# MiniScope.net
KiCad netlist of a schematic drawn in Altium Designer
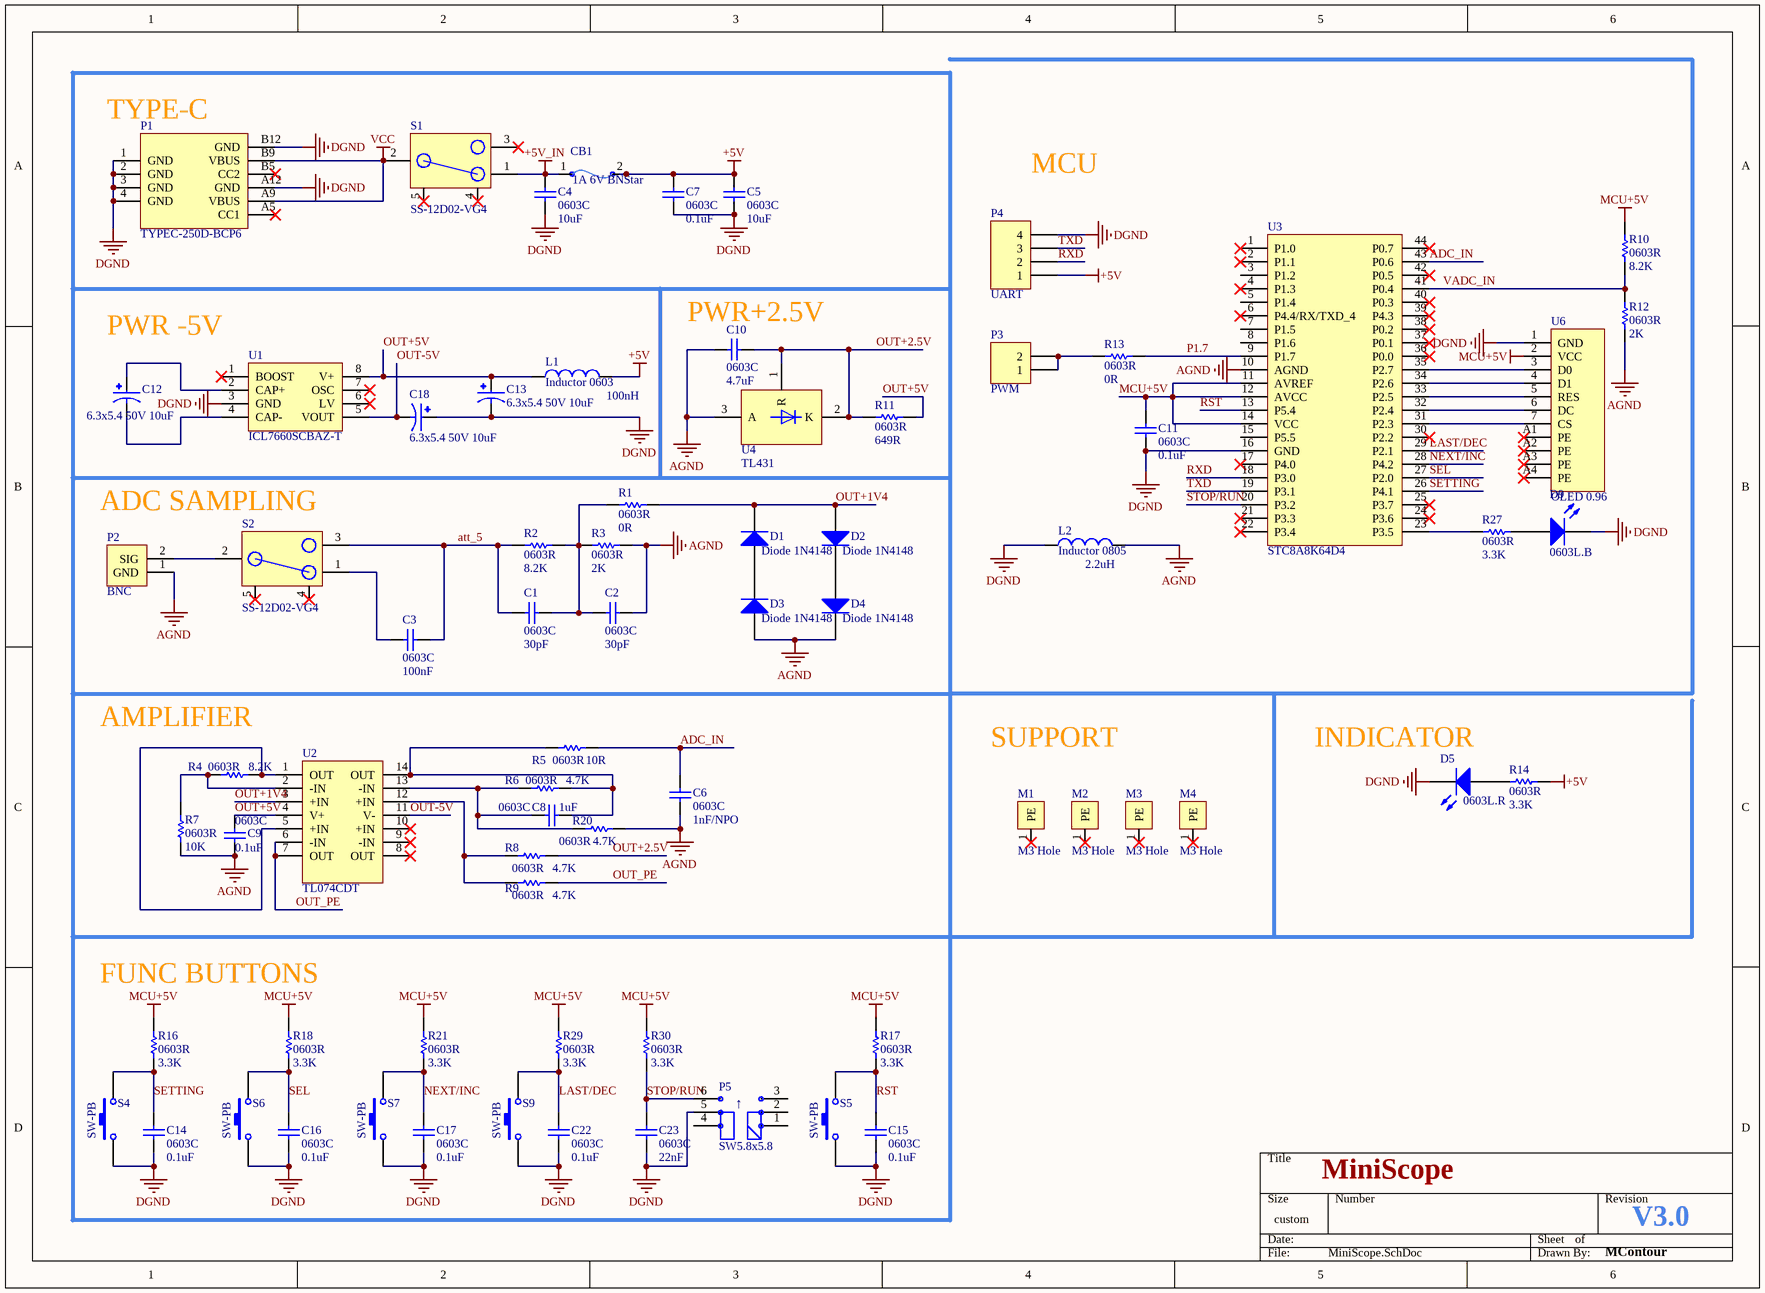
[diagram p0: MiniScope.SchDoc]

(export (version "E")
  (design (tool "Eeschema 10.0.6"))
  (components
    (comp (ref "C1")
      (value "0603C")
      (footprint "0603C")
      (description "Capacitor")
      (fields (field (name "ALTIUM_VALUE") "30pF") (field (name "PUBLISHER") "Altium Limited"))
      (libsource (lib "Miscellaneous Devices") (part "Cap"))
    )
    (comp (ref "C2")
      (value "0603C")
      (footprint "0603C")
      (description "Capacitor")
      (fields (field (name "ALTIUM_VALUE") "30pF") (field (name "PUBLISHER") "Altium Limited"))
      (libsource (lib "Miscellaneous Devices") (part "Cap"))
    )
    (comp (ref "C3")
      (value "0603C")
      (footprint "0603C")
      (description "Capacitor")
      (fields (field (name "ALTIUM_VALUE") "100nF") (field (name "PUBLISHER") "Altium Limited"))
      (libsource (lib "Miscellaneous Devices") (part "Cap"))
    )
    (comp (ref "C4")
      (value "0603C")
      (footprint "0603C")
      (description "Capacitor")
      (fields (field (name "ALTIUM_VALUE") "10uF") (field (name "PUBLISHER") "Altium Limited"))
      (libsource (lib "Miscellaneous Devices") (part "Cap"))
    )
    (comp (ref "C5")
      (value "0603C")
      (footprint "0603C")
      (description "Capacitor")
      (fields (field (name "ALTIUM_VALUE") "10uF") (field (name "PUBLISHER") "Altium Limited"))
      (libsource (lib "Miscellaneous Devices") (part "Cap"))
    )
    (comp (ref "C6")
      (value "0603C")
      (footprint "0603C")
      (description "Capacitor")
      (fields (field (name "ALTIUM_VALUE") "1nF/NPO") (field (name "PUBLISHER") "Altium Limited"))
      (libsource (lib "Miscellaneous Devices") (part "Cap"))
    )
    (comp (ref "C7")
      (value "0603C")
      (footprint "0603C")
      (description "Capacitor")
      (fields (field (name "ALTIUM_VALUE") "0.1uF") (field (name "PUBLISHER") "Altium Limited"))
      (libsource (lib "Miscellaneous Devices") (part "Cap"))
    )
    (comp (ref "C8")
      (value "0603C")
      (footprint "0603C")
      (description "Capacitor")
      (fields (field (name "ALTIUM_VALUE") "1uF") (field (name "PUBLISHER") "Altium Limited"))
      (libsource (lib "Miscellaneous Devices") (part "Cap"))
    )
    (comp (ref "C9")
      (value "0603C")
      (footprint "0603C")
      (description "Capacitor")
      (fields (field (name "ALTIUM_VALUE") "0.1uF") (field (name "PUBLISHER") "Altium Limited"))
      (libsource (lib "Miscellaneous Devices") (part "Cap"))
    )
    (comp (ref "C10")
      (value "0603C")
      (footprint "0603C")
      (description "Capacitor")
      (fields (field (name "ALTIUM_VALUE") "4.7uF") (field (name "PUBLISHER") "Altium Limited"))
      (libsource (lib "Miscellaneous Devices") (part "Cap"))
    )
    (comp (ref "C11")
      (value "0603C")
      (footprint "0603C")
      (description "Capacitor")
      (fields (field (name "ALTIUM_VALUE") "0.1uF") (field (name "PUBLISHER") "Altium Limited"))
      (libsource (lib "Miscellaneous Devices") (part "Cap"))
    )
    (comp (ref "C12")
      (value "6.3x5.4 50V 10uF")
      (footprint "CAP 6.3x5.4")
      (description "Cap Aluminum Lytic 10uF 50V 20% (6.3 X 5.4mm) SMD")
      (fields (field (name "MF") "Panasonic") (field (name "MP") "EEE-1AA330NP"))
      (libsource (lib "MiniScope") (part "6.3x5.4 50V 10uF"))
    )
    (comp (ref "C13")
      (value "6.3x5.4 50V 10uF")
      (footprint "CAP 6.3x5.4")
      (description "Cap Aluminum Lytic 10uF 50V 20% (6.3 X 5.4mm) SMD")
      (fields (field (name "MF") "Panasonic") (field (name "MP") "EEE-1AA330NP"))
      (libsource (lib "MiniScope") (part "6.3x5.4 50V 10uF"))
    )
    (comp (ref "C14")
      (value "0603C")
      (footprint "0603C")
      (description "Capacitor")
      (fields (field (name "ALTIUM_VALUE") "0.1uF") (field (name "PUBLISHER") "Altium Limited"))
      (libsource (lib "Miscellaneous Devices") (part "Cap"))
    )
    (comp (ref "C15")
      (value "0603C")
      (footprint "0603C")
      (description "Capacitor")
      (fields (field (name "ALTIUM_VALUE") "0.1uF") (field (name "PUBLISHER") "Altium Limited"))
      (libsource (lib "Miscellaneous Devices") (part "Cap"))
    )
    (comp (ref "C16")
      (value "0603C")
      (footprint "0603C")
      (description "Capacitor")
      (fields (field (name "ALTIUM_VALUE") "0.1uF") (field (name "PUBLISHER") "Altium Limited"))
      (libsource (lib "Miscellaneous Devices") (part "Cap"))
    )
    (comp (ref "C17")
      (value "0603C")
      (footprint "0603C")
      (description "Capacitor")
      (fields (field (name "ALTIUM_VALUE") "0.1uF") (field (name "PUBLISHER") "Altium Limited"))
      (libsource (lib "Miscellaneous Devices") (part "Cap"))
    )
    (comp (ref "C18")
      (value "6.3x5.4 50V 10uF")
      (footprint "CAP 6.3x5.4")
      (description "Cap Aluminum Lytic 10uF 50V 20% (6.3 X 5.4mm) SMD")
      (fields (field (name "MF") "Panasonic") (field (name "MP") "EEE-1AA330NP"))
      (libsource (lib "") (part "6.3x5.4 50V 10uF_1"))
    )
    (comp (ref "C22")
      (value "0603C")
      (footprint "0603C")
      (description "Capacitor")
      (fields (field (name "ALTIUM_VALUE") "0.1uF") (field (name "PUBLISHER") "Altium Limited"))
      (libsource (lib "Miscellaneous Devices") (part "Cap"))
    )
    (comp (ref "C23")
      (value "0603C")
      (footprint "0603C")
      (description "Capacitor")
      (fields (field (name "ALTIUM_VALUE") "22nF") (field (name "PUBLISHER") "Altium Limited"))
      (libsource (lib "Miscellaneous Devices") (part "Cap"))
    )
    (comp (ref "CB1")
      (value "1A 6V BNStar")
      (footprint "SMD0603")
      (libsource (lib "MiniScope") (part "CircuitBreaker"))
    )
    (comp (ref "D1")
      (value "Diode 1N4148")
      (footprint "1N4148W")
      (description "High Conductance Fast Diode")
      (fields (field (name "PUBLISHER") "Altium Limited"))
      (libsource (lib "Miscellaneous Devices") (part "Diode 1N4148"))
    )
    (comp (ref "D2")
      (value "Diode 1N4148")
      (footprint "1N4148W")
      (description "High Conductance Fast Diode")
      (fields (field (name "PUBLISHER") "Altium Limited"))
      (libsource (lib "Miscellaneous Devices") (part "Diode 1N4148"))
    )
    (comp (ref "D3")
      (value "Diode 1N4148")
      (footprint "1N4148W")
      (description "High Conductance Fast Diode")
      (fields (field (name "PUBLISHER") "Altium Limited"))
      (libsource (lib "Miscellaneous Devices") (part "Diode 1N4148"))
    )
    (comp (ref "D4")
      (value "Diode 1N4148")
      (footprint "1N4148W")
      (description "High Conductance Fast Diode")
      (fields (field (name "PUBLISHER") "Altium Limited"))
      (libsource (lib "Miscellaneous Devices") (part "Diode 1N4148"))
    )
    (comp (ref "D5")
      (value "0603L.R")
      (footprint "LED 0603")
      (description "Typical INFRARED GaAs LED")
      (fields (field (name "PUBLISHER") "Altium Limited"))
      (libsource (lib "Miscellaneous Devices") (part "LED0"))
    )
    (comp (ref "D9")
      (value "0603L.B")
      (footprint "LED 0603")
      (description "Typical INFRARED GaAs LED")
      (fields (field (name "PUBLISHER") "Altium Limited"))
      (libsource (lib "Miscellaneous Devices") (part "LED0"))
    )
    (comp (ref "L1")
      (value "Inductor 0603")
      (footprint "IND_0603")
      (description "Inductor")
      (fields (field (name "ALTIUM_VALUE") "100nH") (field (name "PUBLISHER") "Altium Limited"))
      (libsource (lib "Miscellaneous Devices") (part "Inductor"))
    )
    (comp (ref "L2")
      (value "Inductor 0805")
      (footprint "IND_0805")
      (description "Inductor")
      (fields (field (name "ALTIUM_VALUE") "2.2uH") (field (name "PUBLISHER") "Altium Limited"))
      (libsource (lib "Miscellaneous Devices") (part "Inductor"))
    )
    (comp (ref "M1") (value "M3 Hole") (footprint "M3 Hole") (libsource (lib "MiniScope") (part "M3 Hole")))
    (comp (ref "M2") (value "M3 Hole") (footprint "M3 Hole") (libsource (lib "MiniScope") (part "M3 Hole")))
    (comp (ref "M3") (value "M3 Hole") (footprint "M3 Hole") (libsource (lib "MiniScope") (part "M3 Hole")))
    (comp (ref "M4") (value "M3 Hole") (footprint "M3 Hole") (libsource (lib "MiniScope") (part "M3 Hole")))
    (comp (ref "P1")
      (value "TYPEC-250D-BCP6")
      (footprint "TYPEC-250D-BCP6")
      (libsource (lib "MiniScope") (part "TYPEC-250D-BCP6"))
    )
    (comp (ref "P2") (value "BNC") (footprint "BNC") (libsource (lib "MiniScope") (part "BNC")))
    (comp (ref "P3")
      (value "PWM")
      (footprint "HEADER-1X2")
      (description "Header, 2-Pin")
      (fields (field (name "PUBLISHER") "Altium Limited"))
      (libsource (lib "Miscellaneous Connectors") (part "Header 2"))
    )
    (comp (ref "P4")
      (value "UART")
      (footprint "HEADER-1X4")
      (description "Header, 4-Pin")
      (fields (field (name "PUBLISHER") "Altium Limited"))
      (libsource (lib "Miscellaneous Connectors") (part "Header 4"))
    )
    (comp (ref "P5")
      (value "SW5.8x5.8")
      (footprint "SW5.8x5.8 SL")
      (libsource (lib "MiniScope") (part "SW5.8x5.8"))
    )
    (comp (ref "R1")
      (value "0603R")
      (footprint "0603R")
      (description "Resistor")
      (fields (field (name "ALTIUM_VALUE") "0R") (field (name "PUBLISHER") "Altium Limited"))
      (libsource (lib "Miscellaneous Devices") (part "Res1"))
    )
    (comp (ref "R2")
      (value "0603R")
      (footprint "0603R")
      (description "Resistor")
      (fields (field (name "ALTIUM_VALUE") "8.2K") (field (name "PUBLISHER") "Altium Limited"))
      (libsource (lib "Miscellaneous Devices") (part "Res1"))
    )
    (comp (ref "R3")
      (value "0603R")
      (footprint "0603R")
      (description "Resistor")
      (fields (field (name "ALTIUM_VALUE") "2K") (field (name "PUBLISHER") "Altium Limited"))
      (libsource (lib "Miscellaneous Devices") (part "Res1"))
    )
    (comp (ref "R4")
      (value "0603R")
      (footprint "0603R")
      (description "Resistor")
      (fields (field (name "ALTIUM_VALUE") "8.2K") (field (name "PUBLISHER") "Altium Limited"))
      (libsource (lib "Miscellaneous Devices") (part "Res1"))
    )
    (comp (ref "R5")
      (value "0603R")
      (footprint "0603R")
      (description "Resistor")
      (fields (field (name "ALTIUM_VALUE") "10R") (field (name "PUBLISHER") "Altium Limited"))
      (libsource (lib "Miscellaneous Devices") (part "Res1"))
    )
    (comp (ref "R6")
      (value "0603R")
      (footprint "0603R")
      (description "Resistor")
      (fields (field (name "ALTIUM_VALUE") "4.7K") (field (name "PUBLISHER") "Altium Limited"))
      (libsource (lib "Miscellaneous Devices") (part "Res1"))
    )
    (comp (ref "R7")
      (value "0603R")
      (footprint "0603R")
      (description "Resistor")
      (fields (field (name "ALTIUM_VALUE") "10K") (field (name "PUBLISHER") "Altium Limited"))
      (libsource (lib "Miscellaneous Devices") (part "Res1"))
    )
    (comp (ref "R8")
      (value "0603R")
      (footprint "0603R")
      (description "Resistor")
      (fields (field (name "ALTIUM_VALUE") "4.7K") (field (name "PUBLISHER") "Altium Limited"))
      (libsource (lib "Miscellaneous Devices") (part "Res1"))
    )
    (comp (ref "R9")
      (value "0603R")
      (footprint "0603R")
      (description "Resistor")
      (fields (field (name "ALTIUM_VALUE") "4.7K") (field (name "PUBLISHER") "Altium Limited"))
      (libsource (lib "Miscellaneous Devices") (part "Res1"))
    )
    (comp (ref "R10")
      (value "0603R")
      (footprint "0603R")
      (description "Resistor")
      (fields (field (name "ALTIUM_VALUE") "8.2K") (field (name "PUBLISHER") "Altium Limited"))
      (libsource (lib "Miscellaneous Devices") (part "Res1"))
    )
    (comp (ref "R11")
      (value "0603R")
      (footprint "0603R")
      (description "Resistor")
      (fields (field (name "ALTIUM_UNNAMED_1") "649R") (field (name "PUBLISHER") "Altium Limited"))
      (libsource (lib "Miscellaneous Devices") (part "Res1"))
    )
    (comp (ref "R12")
      (value "0603R")
      (footprint "0603R")
      (description "Resistor")
      (fields (field (name "ALTIUM_VALUE") "2K") (field (name "PUBLISHER") "Altium Limited"))
      (libsource (lib "Miscellaneous Devices") (part "Res1"))
    )
    (comp (ref "R13")
      (value "0603R")
      (footprint "0603R")
      (description "Resistor")
      (fields (field (name "ALTIUM_VALUE") "0R") (field (name "PUBLISHER") "Altium Limited"))
      (libsource (lib "Miscellaneous Devices") (part "Res1"))
    )
    (comp (ref "R14")
      (value "0603R")
      (footprint "0603R")
      (description "Resistor")
      (fields (field (name "ALTIUM_VALUE") "3.3K") (field (name "PUBLISHER") "Altium Limited"))
      (libsource (lib "Miscellaneous Devices") (part "Res1"))
    )
    (comp (ref "R16")
      (value "0603R")
      (footprint "0603R")
      (description "Resistor")
      (fields (field (name "ALTIUM_VALUE") "3.3K") (field (name "PUBLISHER") "Altium Limited"))
      (libsource (lib "Miscellaneous Devices") (part "Res1"))
    )
    (comp (ref "R17")
      (value "0603R")
      (footprint "0603R")
      (description "Resistor")
      (fields (field (name "ALTIUM_VALUE") "3.3K") (field (name "PUBLISHER") "Altium Limited"))
      (libsource (lib "Miscellaneous Devices") (part "Res1"))
    )
    (comp (ref "R18")
      (value "0603R")
      (footprint "0603R")
      (description "Resistor")
      (fields (field (name "ALTIUM_VALUE") "3.3K") (field (name "PUBLISHER") "Altium Limited"))
      (libsource (lib "Miscellaneous Devices") (part "Res1"))
    )
    (comp (ref "R20")
      (value "0603R")
      (footprint "0603R")
      (description "Resistor")
      (fields (field (name "ALTIUM_VALUE") "4.7K") (field (name "PUBLISHER") "Altium Limited"))
      (libsource (lib "Miscellaneous Devices") (part "Res1"))
    )
    (comp (ref "R21")
      (value "0603R")
      (footprint "0603R")
      (description "Resistor")
      (fields (field (name "ALTIUM_VALUE") "3.3K") (field (name "PUBLISHER") "Altium Limited"))
      (libsource (lib "Miscellaneous Devices") (part "Res1"))
    )
    (comp (ref "R27")
      (value "0603R")
      (footprint "0603R")
      (description "Resistor")
      (fields (field (name "ALTIUM_VALUE") "3.3K") (field (name "PUBLISHER") "Altium Limited"))
      (libsource (lib "Miscellaneous Devices") (part "Res1"))
    )
    (comp (ref "R29")
      (value "0603R")
      (footprint "0603R")
      (description "Resistor")
      (fields (field (name "ALTIUM_VALUE") "3.3K") (field (name "PUBLISHER") "Altium Limited"))
      (libsource (lib "Miscellaneous Devices") (part "Res1"))
    )
    (comp (ref "R30")
      (value "0603R")
      (footprint "0603R")
      (description "Resistor")
      (fields (field (name "ALTIUM_VALUE") "3.3K") (field (name "PUBLISHER") "Altium Limited"))
      (libsource (lib "Miscellaneous Devices") (part "Res1"))
    )
    (comp (ref "S1")
      (value "SS-12D02-VG4")
      (footprint "SS-12D02-VG4")
      (libsource (lib "MiniScope") (part "SS-12D02-VG4"))
    )
    (comp (ref "S2")
      (value "SS-12D02-VG4")
      (footprint "SS-12D02-VG4")
      (libsource (lib "MiniScope") (part "SS-12D02-VG4"))
    )
    (comp (ref "S4")
      (value "SW-PB")
      (footprint "SW_3.6×6.1x2.5_smd")
      (description "Switch")
      (fields (field (name "PUBLISHER") "Altium Limited"))
      (libsource (lib "Miscellaneous Devices") (part "SW-PB"))
    )
    (comp (ref "S5")
      (value "SW-PB")
      (footprint "SW_3.6×6.1x2.5_smd")
      (description "Switch")
      (fields (field (name "PUBLISHER") "Altium Limited"))
      (libsource (lib "Miscellaneous Devices") (part "SW-PB"))
    )
    (comp (ref "S6")
      (value "SW-PB")
      (footprint "SW_3.6×6.1x2.5_smd")
      (description "Switch")
      (fields (field (name "PUBLISHER") "Altium Limited"))
      (libsource (lib "Miscellaneous Devices") (part "SW-PB"))
    )
    (comp (ref "S7")
      (value "SW-PB")
      (footprint "SW_3.6×6.1x2.5_smd")
      (description "Switch")
      (fields (field (name "PUBLISHER") "Altium Limited"))
      (libsource (lib "Miscellaneous Devices") (part "SW-PB"))
    )
    (comp (ref "S9")
      (value "SW-PB")
      (footprint "SW_3.6×6.1x2.5_smd")
      (description "Switch")
      (fields (field (name "PUBLISHER") "Altium Limited"))
      (libsource (lib "Miscellaneous Devices") (part "SW-PB"))
    )
    (comp (ref "U1")
      (value "ICL7660SCBAZ-T")
      (footprint "ICL7660SCBAZ-T")
      (libsource (lib "MiniScope") (part "ICL7660SCBAZ-T"))
    )
    (comp (ref "U2")
      (value "TL074CDT")
      (footprint "TL074CDT")
      (libsource (lib "MiniScope") (part "TL074CDT"))
    )
    (comp (ref "U3")
      (value "STC8A8K64D4")
      (footprint "STC8A8K64D4")
      (libsource (lib "MiniScope") (part "STC8A8K64S4A12"))
    )
    (comp (ref "U4") (value "TL431") (footprint "TL431") (libsource (lib "MiniScope") (part "TL431")))
    (comp (ref "U6")
      (value "OLED 0.96")
      (footprint "OLED 0.96ch")
      (libsource (lib "MiniScope") (part "OLED 0.96"))
    )
  )
  (nets
    (net (code "1") (name "+5V") (class "Default")
      (node (ref "C5") (pin "2") (pinfunction "2_2") (pintype "passive"))
      (node (ref "C7") (pin "2") (pinfunction "2_2") (pintype "passive"))
      (node (ref "CB1") (pin "2") (pinfunction "PE_2") (pintype "passive"))
      (node (ref "L1") (pin "2") (pinfunction "2_2") (pintype "passive"))
      (node (ref "P4") (pin "1") (pinfunction "1_1") (pintype "passive"))
      (node (ref "R14") (pin "1") (pinfunction "1_1") (pintype "passive"))
    )
    (net (code "2") (name "+5V_IN") (class "Default")
      (node (ref "C4") (pin "2") (pinfunction "2_2") (pintype "passive"))
      (node (ref "CB1") (pin "1") (pinfunction "PE_1") (pintype "passive"))
      (node (ref "S1") (pin "1") (pinfunction "74_1") (pintype "passive"))
    )
    (net (code "3") (name "/ADC_IN") (class "Default")
      (node (ref "C6") (pin "1") (pinfunction "1_1") (pintype "passive"))
      (node (ref "R5") (pin "2") (pinfunction "2_2") (pintype "passive"))
      (node (ref "U3") (pin "43") (pinfunction "P0.6_43") (pintype "passive"))
    )
    (net (code "4") (name "/LAST{slash}DEC") (class "Default")
      (node (ref "C22") (pin "1") (pinfunction "1_1") (pintype "passive"))
      (node (ref "R29") (pin "1") (pinfunction "1_1") (pintype "passive"))
      (node (ref "S9") (pin "2") (pinfunction "2_2") (pintype "passive"))
      (node (ref "U3") (pin "29") (pinfunction "P2.1_29") (pintype "passive"))
    )
    (net (code "5") (name "/NEXT{slash}INC") (class "Default")
      (node (ref "C17") (pin "1") (pinfunction "1_1") (pintype "passive"))
      (node (ref "R21") (pin "1") (pinfunction "1_1") (pintype "passive"))
      (node (ref "S7") (pin "2") (pinfunction "2_2") (pintype "passive"))
      (node (ref "U3") (pin "28") (pinfunction "P4.2_28") (pintype "passive"))
    )
    (net (code "6") (name "/OUT+1V4") (class "Default")
      (node (ref "D1") (pin "2") (pinfunction "K_2") (pintype "passive"))
      (node (ref "D2") (pin "1") (pinfunction "A_1") (pintype "passive"))
      (node (ref "R1") (pin "1") (pinfunction "1_1") (pintype "passive"))
      (node (ref "U2") (pin "3") (pinfunction "+IN_3") (pintype "passive"))
    )
    (net (code "7") (name "/OUT+2.5V") (class "Default")
      (node (ref "C10") (pin "1") (pinfunction "1_1") (pintype "passive"))
      (node (ref "R11") (pin "1") (pinfunction "1_1") (pintype "passive"))
      (node (ref "R8") (pin "2") (pinfunction "2_2") (pintype "passive"))
      (node (ref "U4") (pin "1") (pinfunction "R_1") (pintype "passive"))
      (node (ref "U4") (pin "2") (pinfunction "K_2") (pintype "passive"))
    )
    (net (code "8") (name "/OUT+5V") (class "Default")
      (node (ref "C13") (pin "1") (pinfunction "1_1") (pintype "passive"))
      (node (ref "C9") (pin "1") (pinfunction "1_1") (pintype "passive"))
      (node (ref "L1") (pin "1") (pinfunction "1_1") (pintype "passive"))
      (node (ref "R11") (pin "2") (pinfunction "2_2") (pintype "passive"))
      (node (ref "U1") (pin "8") (pinfunction "V+_8") (pintype "passive"))
      (node (ref "U2") (pin "4") (pinfunction "V+_4") (pintype "passive"))
    )
    (net (code "9") (name "/OUT-5V") (class "Default")
      (node (ref "C18") (pin "2") (pinfunction "2_2") (pintype "passive"))
      (node (ref "U1") (pin "5") (pinfunction "VOUT_5") (pintype "passive"))
      (node (ref "U2") (pin "11") (pinfunction "V-_11") (pintype "passive"))
    )
    (net (code "10") (name "/OUT_PE") (class "Default")
      (node (ref "R9") (pin "2") (pinfunction "2_2") (pintype "passive"))
      (node (ref "U2") (pin "6") (pinfunction "-IN_6") (pintype "passive"))
      (node (ref "U2") (pin "7") (pinfunction "OUT_7") (pintype "passive"))
    )
    (net (code "11") (name "/P1.7") (class "Default")
      (node (ref "R13") (pin "1") (pinfunction "1_1") (pintype "passive"))
      (node (ref "U3") (pin "9") (pinfunction "P1.7_9") (pintype "passive"))
    )
    (net (code "12") (name "/RST") (class "Default")
      (node (ref "C15") (pin "1") (pinfunction "1_1") (pintype "passive"))
      (node (ref "R17") (pin "1") (pinfunction "1_1") (pintype "passive"))
      (node (ref "S5") (pin "2") (pinfunction "2_2") (pintype "passive"))
      (node (ref "U3") (pin "13") (pinfunction "P5.4_13") (pintype "passive"))
    )
    (net (code "13") (name "/RXD") (class "Default")
      (node (ref "P4") (pin "2") (pinfunction "2_2") (pintype "passive"))
      (node (ref "U3") (pin "18") (pinfunction "P3.0_18") (pintype "passive"))
    )
    (net (code "14") (name "/SEL") (class "Default")
      (node (ref "C16") (pin "1") (pinfunction "1_1") (pintype "passive"))
      (node (ref "R18") (pin "1") (pinfunction "1_1") (pintype "passive"))
      (node (ref "S6") (pin "2") (pinfunction "2_2") (pintype "passive"))
      (node (ref "U3") (pin "27") (pinfunction "P2.0_27") (pintype "passive"))
    )
    (net (code "15") (name "/SETTING") (class "Default")
      (node (ref "C14") (pin "1") (pinfunction "1_1") (pintype "passive"))
      (node (ref "R16") (pin "1") (pinfunction "1_1") (pintype "passive"))
      (node (ref "S4") (pin "2") (pinfunction "2_2") (pintype "passive"))
      (node (ref "U3") (pin "26") (pinfunction "P4.1_26") (pintype "passive"))
    )
    (net (code "16") (name "/STOP{slash}RUN") (class "Default")
      (node (ref "C23") (pin "1") (pinfunction "1_1") (pintype "passive"))
      (node (ref "P5") (pin "6") (pinfunction "6_6") (pintype "passive"))
      (node (ref "R30") (pin "1") (pinfunction "1_1") (pintype "passive"))
      (node (ref "U3") (pin "20") (pinfunction "P3.2_20") (pintype "passive"))
    )
    (net (code "17") (name "/TXD") (class "Default")
      (node (ref "P4") (pin "3") (pinfunction "3_3") (pintype "passive"))
      (node (ref "U3") (pin "19") (pinfunction "P3.1_19") (pintype "passive"))
    )
    (net (code "18") (name "/VADC_IN") (class "Default")
      (node (ref "R10") (pin "2") (pinfunction "2_2") (pintype "passive"))
      (node (ref "R12") (pin "1") (pinfunction "1_1") (pintype "passive"))
      (node (ref "U3") (pin "41") (pinfunction "P0.4_41") (pintype "passive"))
    )
    (net (code "19") (name "/att_5") (class "Default")
      (node (ref "C1") (pin "1") (pinfunction "1_1") (pintype "passive"))
      (node (ref "C3") (pin "2") (pinfunction "2_2") (pintype "passive"))
      (node (ref "R2") (pin "2") (pinfunction "2_2") (pintype "passive"))
      (node (ref "S2") (pin "3") (pinfunction "75_3") (pintype "passive"))
    )
    (net (code "20") (name "AGND") (class "Default")
      (node (ref "C10") (pin "2") (pinfunction "2_2") (pintype "passive"))
      (node (ref "C2") (pin "2") (pinfunction "2_2") (pintype "passive"))
      (node (ref "C6") (pin "2") (pinfunction "2_2") (pintype "passive"))
      (node (ref "C9") (pin "2") (pinfunction "2_2") (pintype "passive"))
      (node (ref "D3") (pin "1") (pinfunction "A_1") (pintype "passive"))
      (node (ref "D4") (pin "2") (pinfunction "K_2") (pintype "passive"))
      (node (ref "L2") (pin "2") (pinfunction "2_2") (pintype "passive"))
      (node (ref "P2") (pin "1") (pinfunction "GND_1") (pintype "passive"))
      (node (ref "R12") (pin "2") (pinfunction "2_2") (pintype "passive"))
      (node (ref "R20") (pin "2") (pinfunction "2_2") (pintype "passive"))
      (node (ref "R3") (pin "1") (pinfunction "1_1") (pintype "passive"))
      (node (ref "R7") (pin "2") (pinfunction "2_2") (pintype "passive"))
      (node (ref "U3") (pin "10") (pinfunction "AGND_10") (pintype "passive"))
      (node (ref "U4") (pin "3") (pinfunction "A_3") (pintype "passive"))
    )
    (net (code "21") (name "DGND") (class "Default")
      (node (ref "C11") (pin "2") (pinfunction "2_2") (pintype "passive"))
      (node (ref "C13") (pin "2") (pinfunction "2_2") (pintype "passive"))
      (node (ref "C14") (pin "2") (pinfunction "2_2") (pintype "passive"))
      (node (ref "C15") (pin "2") (pinfunction "2_2") (pintype "passive"))
      (node (ref "C16") (pin "2") (pinfunction "2_2") (pintype "passive"))
      (node (ref "C17") (pin "2") (pinfunction "2_2") (pintype "passive"))
      (node (ref "C18") (pin "1") (pinfunction "1_1") (pintype "passive"))
      (node (ref "C22") (pin "2") (pinfunction "2_2") (pintype "passive"))
      (node (ref "C23") (pin "2") (pinfunction "2_2") (pintype "passive"))
      (node (ref "C4") (pin "1") (pinfunction "1_1") (pintype "passive"))
      (node (ref "C5") (pin "1") (pinfunction "1_1") (pintype "passive"))
      (node (ref "C7") (pin "1") (pinfunction "1_1") (pintype "passive"))
      (node (ref "D5") (pin "2") (pinfunction "K_2") (pintype "passive"))
      (node (ref "D9") (pin "2") (pinfunction "K_2") (pintype "passive"))
      (node (ref "L2") (pin "1") (pinfunction "1_1") (pintype "passive"))
      (node (ref "P1") (pin "1") (pinfunction "GND_1") (pintype "passive"))
      (node (ref "P1") (pin "2") (pinfunction "GND_2") (pintype "passive"))
      (node (ref "P1") (pin "3") (pinfunction "GND_3") (pintype "passive"))
      (node (ref "P1") (pin "4") (pinfunction "GND_4") (pintype "passive"))
      (node (ref "P1") (pin "A12") (pinfunction "GND_A12") (pintype "passive"))
      (node (ref "P1") (pin "B12") (pinfunction "GND_B12") (pintype "passive"))
      (node (ref "P4") (pin "4") (pinfunction "4_4") (pintype "passive"))
      (node (ref "P5") (pin "5") (pinfunction "5_5") (pintype "passive"))
      (node (ref "S4") (pin "1") (pinfunction "1_1") (pintype "passive"))
      (node (ref "S5") (pin "1") (pinfunction "1_1") (pintype "passive"))
      (node (ref "S6") (pin "1") (pinfunction "1_1") (pintype "passive"))
      (node (ref "S7") (pin "1") (pinfunction "1_1") (pintype "passive"))
      (node (ref "S9") (pin "1") (pinfunction "1_1") (pintype "passive"))
      (node (ref "U1") (pin "3") (pinfunction "GND_3") (pintype "passive"))
      (node (ref "U3") (pin "16") (pinfunction "GND_16") (pintype "passive"))
      (node (ref "U6") (pin "1") (pinfunction "GND_1") (pintype "passive"))
    )
    (net (code "22") (name "MCU+5V") (class "Default")
      (node (ref "C11") (pin "1") (pinfunction "1_1") (pintype "passive"))
      (node (ref "R10") (pin "1") (pinfunction "1_1") (pintype "passive"))
      (node (ref "R16") (pin "2") (pinfunction "2_2") (pintype "passive"))
      (node (ref "R17") (pin "2") (pinfunction "2_2") (pintype "passive"))
      (node (ref "R18") (pin "2") (pinfunction "2_2") (pintype "passive"))
      (node (ref "R21") (pin "2") (pinfunction "2_2") (pintype "passive"))
      (node (ref "R29") (pin "2") (pinfunction "2_2") (pintype "passive"))
      (node (ref "R30") (pin "2") (pinfunction "2_2") (pintype "passive"))
      (node (ref "U3") (pin "11") (pinfunction "AVREF_11") (pintype "passive"))
      (node (ref "U3") (pin "12") (pinfunction "AVCC_12") (pintype "passive"))
      (node (ref "U3") (pin "14") (pinfunction "VCC_14") (pintype "passive"))
      (node (ref "U6") (pin "2") (pinfunction "VCC_2") (pintype "passive"))
    )
    (net (code "23") (name "Net-(C1-Pad2)") (class "Default")
      (node (ref "C1") (pin "2") (pinfunction "2_2") (pintype "passive"))
      (node (ref "C2") (pin "1") (pinfunction "1_1") (pintype "passive"))
      (node (ref "R1") (pin "2") (pinfunction "2_2") (pintype "passive"))
      (node (ref "R2") (pin "1") (pinfunction "1_1") (pintype "passive"))
      (node (ref "R3") (pin "2") (pinfunction "2_2") (pintype "passive"))
    )
    (net (code "24") (name "Net-(C8-Pad1)") (class "Default")
      (node (ref "C8") (pin "1") (pinfunction "1_1") (pintype "passive"))
      (node (ref "R20") (pin "1") (pinfunction "1_1") (pintype "passive"))
      (node (ref "R6") (pin "1") (pinfunction "1_1") (pintype "passive"))
      (node (ref "U2") (pin "13") (pinfunction "-IN_13") (pintype "passive"))
    )
    (net (code "25") (name "Net-(C8-Pad2)") (class "Default")
      (node (ref "C8") (pin "2") (pinfunction "2_2") (pintype "passive"))
      (node (ref "R5") (pin "1") (pinfunction "1_1") (pintype "passive"))
      (node (ref "R6") (pin "2") (pinfunction "2_2") (pintype "passive"))
      (node (ref "U2") (pin "14") (pinfunction "OUT_14") (pintype "passive"))
    )
    (net (code "26") (name "Net-(D1-A)") (class "Default")
      (node (ref "D1") (pin "1") (pinfunction "A_1") (pintype "passive"))
      (node (ref "D3") (pin "2") (pinfunction "K_2") (pintype "passive"))
    )
    (net (code "27") (name "Net-(D2-K)") (class "Default")
      (node (ref "D2") (pin "2") (pinfunction "K_2") (pintype "passive"))
      (node (ref "D4") (pin "1") (pinfunction "A_1") (pintype "passive"))
    )
    (net (code "28") (name "Net-(D5-A)") (class "Default")
      (node (ref "D5") (pin "1") (pinfunction "A_1") (pintype "passive"))
      (node (ref "R14") (pin "2") (pinfunction "2_2") (pintype "passive"))
    )
    (net (code "29") (name "Net-(D9-A)") (class "Default")
      (node (ref "D9") (pin "1") (pinfunction "A_1") (pintype "passive"))
      (node (ref "R27") (pin "2") (pinfunction "2_2") (pintype "passive"))
    )
    (net (code "30") (name "Net-(P2-SIG)") (class "Default")
      (node (ref "P2") (pin "2") (pinfunction "SIG_2") (pintype "passive"))
      (node (ref "S2") (pin "2") (pinfunction "71_2") (pintype "passive"))
    )
    (net (code "31") (name "Net-(P3-Pad1)") (class "Default")
      (node (ref "P3") (pin "1") (pinfunction "1_1") (pintype "passive"))
      (node (ref "P3") (pin "2") (pinfunction "2_2") (pintype "passive"))
      (node (ref "R13") (pin "2") (pinfunction "2_2") (pintype "passive"))
    )
    (net (code "32") (name "Net-(R4-Pad1)") (class "Default")
      (node (ref "R4") (pin "1") (pinfunction "1_1") (pintype "passive"))
      (node (ref "U2") (pin "1") (pinfunction "OUT_1") (pintype "passive"))
      (node (ref "U2") (pin "5") (pinfunction "+IN_5") (pintype "passive"))
    )
    (net (code "33") (name "Net-(R4-Pad2)") (class "Default")
      (node (ref "R4") (pin "2") (pinfunction "2_2") (pintype "passive"))
      (node (ref "R7") (pin "1") (pinfunction "1_1") (pintype "passive"))
      (node (ref "U2") (pin "2") (pinfunction "-IN_2") (pintype "passive"))
    )
    (net (code "34") (name "Net-(R8-Pad1)") (class "Default")
      (node (ref "R8") (pin "1") (pinfunction "1_1") (pintype "passive"))
      (node (ref "R9") (pin "1") (pinfunction "1_1") (pintype "passive"))
      (node (ref "U2") (pin "12") (pinfunction "+IN_12") (pintype "passive"))
    )
    (net (code "35") (name "Net-(S2-74)") (class "Default")
      (node (ref "C3") (pin "1") (pinfunction "1_1") (pintype "passive"))
      (node (ref "S2") (pin "1") (pinfunction "74_1") (pintype "passive"))
    )
    (net (code "36") (name "Net-(U1-CAP+)") (class "Default")
      (node (ref "C12") (pin "1") (pinfunction "1_1") (pintype "passive"))
      (node (ref "U1") (pin "2") (pinfunction "CAP+_2") (pintype "passive"))
    )
    (net (code "37") (name "Net-(U1-CAP-)") (class "Default")
      (node (ref "C12") (pin "2") (pinfunction "2_2") (pintype "passive"))
      (node (ref "U1") (pin "4") (pinfunction "CAP-_4") (pintype "passive"))
    )
    (net (code "38") (name "Net-(U3-P2.3)") (class "Default")
      (node (ref "U3") (pin "31") (pinfunction "P2.3_31") (pintype "passive"))
      (node (ref "U6") (pin "7") (pinfunction "CS_7") (pintype "passive"))
    )
    (net (code "39") (name "Net-(U3-P2.4)") (class "Default")
      (node (ref "U3") (pin "32") (pinfunction "P2.4_32") (pintype "passive"))
      (node (ref "U6") (pin "6") (pinfunction "DC_6") (pintype "passive"))
    )
    (net (code "40") (name "Net-(U3-P2.5)") (class "Default")
      (node (ref "U3") (pin "33") (pinfunction "P2.5_33") (pintype "passive"))
      (node (ref "U6") (pin "5") (pinfunction "RES_5") (pintype "passive"))
    )
    (net (code "41") (name "Net-(U3-P2.6)") (class "Default")
      (node (ref "U3") (pin "34") (pinfunction "P2.6_34") (pintype "passive"))
      (node (ref "U6") (pin "4") (pinfunction "D1_4") (pintype "passive"))
    )
    (net (code "42") (name "Net-(U3-P2.7)") (class "Default")
      (node (ref "U3") (pin "35") (pinfunction "P2.7_35") (pintype "passive"))
      (node (ref "U6") (pin "3") (pinfunction "D0_3") (pintype "passive"))
    )
    (net (code "43") (name "Net-(U3-P3.5)") (class "Default")
      (node (ref "R27") (pin "1") (pinfunction "1_1") (pintype "passive"))
      (node (ref "U3") (pin "23") (pinfunction "P3.5_23") (pintype "passive"))
    )
    (net (code "44") (name "VCC") (class "Default")
      (node (ref "P1") (pin "A9") (pinfunction "VBUS_A9") (pintype "passive"))
      (node (ref "P1") (pin "B9") (pinfunction "VBUS_B9") (pintype "passive"))
      (node (ref "S1") (pin "2") (pinfunction "71_2") (pintype "passive"))
    )
    (net (code "45") (name "unconnected-(M1-PE-Pad1)") (class "Default")
      (node (ref "M1") (pin "1") (pinfunction "PE_1") (pintype "passive+no_connect"))
    )
    (net (code "46") (name "unconnected-(M2-PE-Pad1)") (class "Default")
      (node (ref "M2") (pin "1") (pinfunction "PE_1") (pintype "passive+no_connect"))
    )
    (net (code "47") (name "unconnected-(M3-PE-Pad1)") (class "Default")
      (node (ref "M3") (pin "1") (pinfunction "PE_1") (pintype "passive+no_connect"))
    )
    (net (code "48") (name "unconnected-(M4-PE-Pad1)") (class "Default")
      (node (ref "M4") (pin "1") (pinfunction "PE_1") (pintype "passive+no_connect"))
    )
    (net (code "49") (name "unconnected-(P1-CC1-PadA5)") (class "Default")
      (node (ref "P1") (pin "A5") (pinfunction "CC1_A5") (pintype "passive+no_connect"))
    )
    (net (code "50") (name "unconnected-(P1-CC2-PadB5)") (class "Default")
      (node (ref "P1") (pin "B5") (pinfunction "CC2_B5") (pintype "passive+no_connect"))
    )
    (net (code "51") (name "unconnected-(P5-EP-Pad1)") (class "Default")
      (node (ref "P5") (pin "1") (pinfunction "EP_1") (pintype "passive"))
    )
    (net (code "52") (name "unconnected-(P5-EP-Pad2)") (class "Default")
      (node (ref "P5") (pin "2") (pinfunction "EP_2") (pintype "passive"))
    )
    (net (code "53") (name "unconnected-(P5-EP-Pad3)") (class "Default")
      (node (ref "P5") (pin "3") (pinfunction "EP_3") (pintype "passive"))
    )
    (net (code "54") (name "unconnected-(P5-Pad4)") (class "Default")
      (node (ref "P5") (pin "4") (pinfunction "4_4") (pintype "passive"))
    )
    (net (code "55") (name "unconnected-(S1-72-Pad5)") (class "Default")
      (node (ref "S1") (pin "5") (pinfunction "72_5") (pintype "passive+no_connect"))
    )
    (net (code "56") (name "unconnected-(S1-73-Pad4)") (class "Default")
      (node (ref "S1") (pin "4") (pinfunction "73_4") (pintype "passive+no_connect"))
    )
    (net (code "57") (name "unconnected-(S1-75-Pad3)") (class "Default")
      (node (ref "S1") (pin "3") (pinfunction "75_3") (pintype "passive+no_connect"))
    )
    (net (code "58") (name "unconnected-(S2-72-Pad5)") (class "Default")
      (node (ref "S2") (pin "5") (pinfunction "72_5") (pintype "passive+no_connect"))
    )
    (net (code "59") (name "unconnected-(S2-73-Pad4)") (class "Default")
      (node (ref "S2") (pin "4") (pinfunction "73_4") (pintype "passive+no_connect"))
    )
    (net (code "60") (name "unconnected-(U1-BOOST-Pad1)") (class "Default")
      (node (ref "U1") (pin "1") (pinfunction "BOOST_1") (pintype "passive+no_connect"))
    )
    (net (code "61") (name "unconnected-(U1-LV-Pad6)") (class "Default")
      (node (ref "U1") (pin "6") (pinfunction "LV_6") (pintype "passive+no_connect"))
    )
    (net (code "62") (name "unconnected-(U1-OSC-Pad7)") (class "Default")
      (node (ref "U1") (pin "7") (pinfunction "OSC_7") (pintype "passive+no_connect"))
    )
    (net (code "63") (name "unconnected-(U2-+IN-Pad10)") (class "Default")
      (node (ref "U2") (pin "10") (pinfunction "+IN_10") (pintype "passive+no_connect"))
    )
    (net (code "64") (name "unconnected-(U2--IN-Pad9)") (class "Default")
      (node (ref "U2") (pin "9") (pinfunction "-IN_9") (pintype "passive+no_connect"))
    )
    (net (code "65") (name "unconnected-(U2-OUT-Pad8)") (class "Default")
      (node (ref "U2") (pin "8") (pinfunction "OUT_8") (pintype "passive+no_connect"))
    )
    (net (code "66") (name "unconnected-(U3-P0.0-Pad36)") (class "Default")
      (node (ref "U3") (pin "36") (pinfunction "P0.0_36") (pintype "passive+no_connect"))
    )
    (net (code "67") (name "unconnected-(U3-P0.1-Pad37)") (class "Default")
      (node (ref "U3") (pin "37") (pinfunction "P0.1_37") (pintype "passive+no_connect"))
    )
    (net (code "68") (name "unconnected-(U3-P0.2-Pad38)") (class "Default")
      (node (ref "U3") (pin "38") (pinfunction "P0.2_38") (pintype "passive+no_connect"))
    )
    (net (code "69") (name "unconnected-(U3-P0.3-Pad40)") (class "Default")
      (node (ref "U3") (pin "40") (pinfunction "P0.3_40") (pintype "passive+no_connect"))
    )
    (net (code "70") (name "unconnected-(U3-P0.5-Pad42)") (class "Default")
      (node (ref "U3") (pin "42") (pinfunction "P0.5_42") (pintype "passive+no_connect"))
    )
    (net (code "71") (name "unconnected-(U3-P0.7-Pad44)") (class "Default")
      (node (ref "U3") (pin "44") (pinfunction "P0.7_44") (pintype "passive+no_connect"))
    )
    (net (code "72") (name "unconnected-(U3-P1.0-Pad1)") (class "Default")
      (node (ref "U3") (pin "1") (pinfunction "P1.0_1") (pintype "passive+no_connect"))
    )
    (net (code "73") (name "unconnected-(U3-P1.1-Pad2)") (class "Default")
      (node (ref "U3") (pin "2") (pinfunction "P1.1_2") (pintype "passive+no_connect"))
    )
    (net (code "74") (name "unconnected-(U3-P1.2-Pad3)") (class "Default")
      (node (ref "U3") (pin "3") (pinfunction "P1.2_3") (pintype "passive"))
    )
    (net (code "75") (name "unconnected-(U3-P1.3-Pad4)") (class "Default")
      (node (ref "U3") (pin "4") (pinfunction "P1.3_4") (pintype "passive+no_connect"))
    )
    (net (code "76") (name "unconnected-(U3-P1.4-Pad5)") (class "Default")
      (node (ref "U3") (pin "5") (pinfunction "P1.4_5") (pintype "passive"))
    )
    (net (code "77") (name "unconnected-(U3-P1.5-Pad7)") (class "Default")
      (node (ref "U3") (pin "7") (pinfunction "P1.5_7") (pintype "passive"))
    )
    (net (code "78") (name "unconnected-(U3-P1.6-Pad8)") (class "Default")
      (node (ref "U3") (pin "8") (pinfunction "P1.6_8") (pintype "passive"))
    )
    (net (code "79") (name "unconnected-(U3-P2.2-Pad30)") (class "Default")
      (node (ref "U3") (pin "30") (pinfunction "P2.2_30") (pintype "passive+no_connect"))
    )
    (net (code "80") (name "unconnected-(U3-P3.3-Pad21)") (class "Default")
      (node (ref "U3") (pin "21") (pinfunction "P3.3_21") (pintype "passive+no_connect"))
    )
    (net (code "81") (name "unconnected-(U3-P3.4-Pad22)") (class "Default")
      (node (ref "U3") (pin "22") (pinfunction "P3.4_22") (pintype "passive+no_connect"))
    )
    (net (code "82") (name "unconnected-(U3-P3.6-Pad24)") (class "Default")
      (node (ref "U3") (pin "24") (pinfunction "P3.6_24") (pintype "passive+no_connect"))
    )
    (net (code "83") (name "unconnected-(U3-P3.7-Pad25)") (class "Default")
      (node (ref "U3") (pin "25") (pinfunction "P3.7_25") (pintype "passive+no_connect"))
    )
    (net (code "84") (name "unconnected-(U3-P4.0-Pad17)") (class "Default")
      (node (ref "U3") (pin "17") (pinfunction "P4.0_17") (pintype "passive+no_connect"))
    )
    (net (code "85") (name "unconnected-(U3-P4.3-Pad39)") (class "Default")
      (node (ref "U3") (pin "39") (pinfunction "P4.3_39") (pintype "passive+no_connect"))
    )
    (net (code "86") (name "unconnected-(U3-P4.4{slash}RX{slash}TXD_4-Pad6)") (class "Default")
      (node (ref "U3") (pin "6") (pinfunction "P4.4/RX/TXD_4_6") (pintype "passive+no_connect"))
    )
    (net (code "87") (name "unconnected-(U3-P5.5-Pad15)") (class "Default")
      (node (ref "U3") (pin "15") (pinfunction "P5.5_15") (pintype "passive"))
    )
    (net (code "88") (name "unconnected-(U6-PE-PadA1)") (class "Default")
      (node (ref "U6") (pin "A1") (pinfunction "PE_A1") (pintype "passive+no_connect"))
    )
    (net (code "89") (name "unconnected-(U6-PE-PadA2)") (class "Default")
      (node (ref "U6") (pin "A2") (pinfunction "PE_A2") (pintype "passive+no_connect"))
    )
    (net (code "90") (name "unconnected-(U6-PE-PadA3)") (class "Default")
      (node (ref "U6") (pin "A3") (pinfunction "PE_A3") (pintype "passive+no_connect"))
    )
    (net (code "91") (name "unconnected-(U6-PE-PadA4)") (class "Default")
      (node (ref "U6") (pin "A4") (pinfunction "PE_A4") (pintype "passive+no_connect"))
    )
  )
)
